# 1M_board.net
KiCad netlist of a schematic drawn in EAGLE
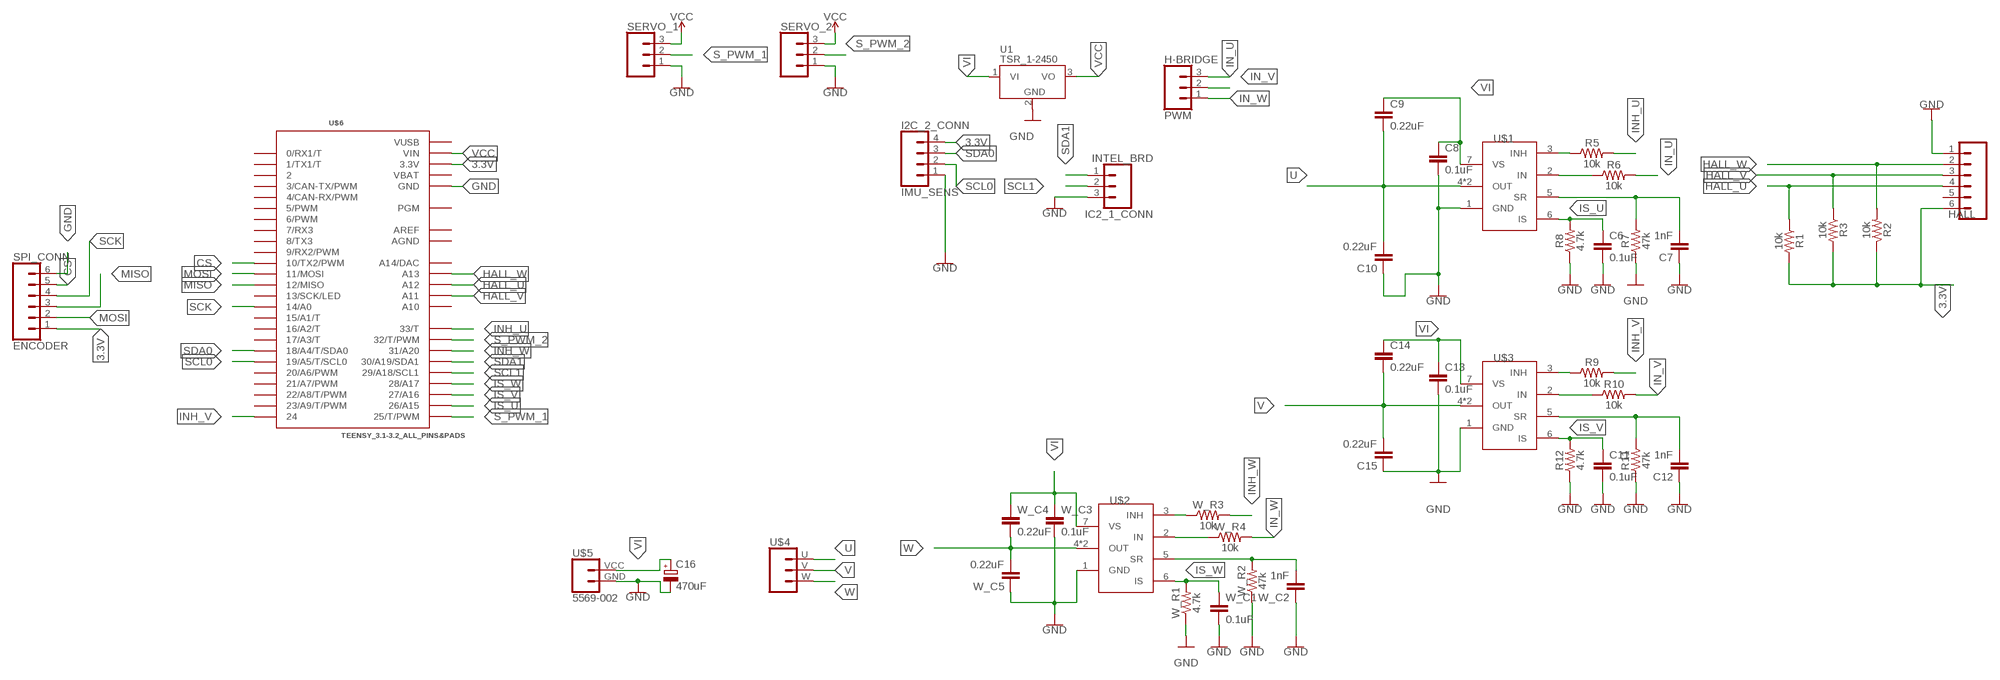
[diagram p0: schematic, sheet 1]

(export (version "E")
  (design (tool "Eeschema 10.0.6"))
  (components
    (comp (ref "C6")
      (value "0.1uF")
      (footprint "eagle-import:0603")
      (libsource (lib "eagle-import") (part "0.1UF-0603-25V-5%"))
    )
    (comp (ref "C7")
      (value "1nF")
      (footprint "eagle-import:0603")
      (libsource (lib "eagle-import") (part "1.0NF/1000PF-0603-50V-10%"))
    )
    (comp (ref "C8")
      (value "0.1uF")
      (footprint "eagle-import:0603")
      (libsource (lib "eagle-import") (part "0.1UF-0603-25V-5%"))
    )
    (comp (ref "C9")
      (value "0.22uF")
      (footprint "eagle-import:0603")
      (libsource (lib "eagle-import") (part "0.22UF-0603-25V-10%"))
    )
    (comp (ref "C10")
      (value "0.22uF")
      (footprint "eagle-import:0603")
      (libsource (lib "eagle-import") (part "0.22UF-0603-25V-10%"))
    )
    (comp (ref "C11")
      (value "0.1uF")
      (footprint "eagle-import:0603")
      (libsource (lib "eagle-import") (part "0.1UF-0603-25V-5%"))
    )
    (comp (ref "C12")
      (value "1nF")
      (footprint "eagle-import:0603")
      (libsource (lib "eagle-import") (part "1.0NF/1000PF-0603-50V-10%"))
    )
    (comp (ref "C13")
      (value "0.1uF")
      (footprint "eagle-import:0603")
      (libsource (lib "eagle-import") (part "0.1UF-0603-25V-5%"))
    )
    (comp (ref "C14")
      (value "0.22uF")
      (footprint "eagle-import:0603")
      (libsource (lib "eagle-import") (part "0.22UF-0603-25V-10%"))
    )
    (comp (ref "C15")
      (value "0.22uF")
      (footprint "eagle-import:0603")
      (libsource (lib "eagle-import") (part "0.22UF-0603-25V-10%"))
    )
    (comp (ref "C16")
      (value "470uF")
      (footprint "eagle-import:E2,5-6E")
      (libsource (lib "eagle-import") (part "CPOL-EUE2,5-6E"))
    )
    (comp (ref "H-BRIDGE")
      (value "PWM")
      (footprint "eagle-import:1X03_NO_SILK")
      (libsource (lib "eagle-import") (part "CONN_031X03_NO_SILK"))
    )
    (comp (ref "HALL")
      (value "CONN_06SMD-1MM")
      (footprint "eagle-import:1X06-1MM")
      (libsource (lib "eagle-import") (part "CONN_06SMD-1MM"))
    )
    (comp (ref "I2C_2_CONN")
      (value "IMU_SENS")
      (footprint "eagle-import:1X04_NO_SILK")
      (libsource (lib "eagle-import") (part "CONN_041X04_NO_SILK"))
    )
    (comp (ref "IC2_1_CONN")
      (value "INTEL_BRD")
      (footprint "eagle-import:1X03_NO_SILK")
      (libsource (lib "eagle-import") (part "CONN_031X03_NO_SILK"))
    )
    (comp (ref "R1")
      (value "10k")
      (footprint "eagle-import:0603")
      (libsource (lib "eagle-import") (part "10KOHM-0603-1/10W-1%"))
    )
    (comp (ref "R2")
      (value "10k")
      (footprint "eagle-import:0603")
      (libsource (lib "eagle-import") (part "10KOHM-0603-1/10W-1%"))
    )
    (comp (ref "R3")
      (value "10k")
      (footprint "eagle-import:0603")
      (libsource (lib "eagle-import") (part "10KOHM-0603-1/10W-1%"))
    )
    (comp (ref "R5")
      (value "10k")
      (footprint "eagle-import:0603")
      (libsource (lib "eagle-import") (part "10KOHM-0603-1/10W-1%"))
    )
    (comp (ref "R6")
      (value "10k")
      (footprint "eagle-import:0603")
      (libsource (lib "eagle-import") (part "10KOHM-0603-1/10W-1%"))
    )
    (comp (ref "R7")
      (value "47k")
      (footprint "eagle-import:0603")
      (libsource (lib "eagle-import") (part "47KOHM-0603-1/10W-1%"))
    )
    (comp (ref "R8")
      (value "4.7k")
      (footprint "eagle-import:0603")
      (libsource (lib "eagle-import") (part "4.7KOHM-0603-1/10W-1%"))
    )
    (comp (ref "R9")
      (value "10k")
      (footprint "eagle-import:0603")
      (libsource (lib "eagle-import") (part "10KOHM-0603-1/10W-1%"))
    )
    (comp (ref "R10")
      (value "10k")
      (footprint "eagle-import:0603")
      (libsource (lib "eagle-import") (part "10KOHM-0603-1/10W-1%"))
    )
    (comp (ref "R11")
      (value "47k")
      (footprint "eagle-import:0603")
      (libsource (lib "eagle-import") (part "47KOHM-0603-1/10W-1%"))
    )
    (comp (ref "R12")
      (value "4.7k")
      (footprint "eagle-import:0603")
      (libsource (lib "eagle-import") (part "4.7KOHM-0603-1/10W-1%"))
    )
    (comp (ref "SERVO_1")
      (value "CONN_031X03_NO_SILK")
      (footprint "eagle-import:1X03_NO_SILK")
      (libsource (lib "eagle-import") (part "CONN_031X03_NO_SILK"))
    )
    (comp (ref "SERVO_2")
      (value "CONN_031X03_NO_SILK")
      (footprint "eagle-import:1X03_NO_SILK")
      (libsource (lib "eagle-import") (part "CONN_031X03_NO_SILK"))
    )
    (comp (ref "SPI_CONN")
      (value "ENCODER")
      (footprint "eagle-import:1X06-1MM")
      (libsource (lib "eagle-import") (part "CONN_06SMD-1MM"))
    )
    (comp (ref "U$1")
      (value "IFX007TZZZZ")
      (footprint "eagle-import:P-TO263-7-1")
      (libsource (lib "eagle-import") (part "IFX007TZZZZ"))
    )
    (comp (ref "U$2")
      (value "IFX007TZZZZ")
      (footprint "eagle-import:P-TO263-7-1")
      (libsource (lib "eagle-import") (part "IFX007TZZZZ"))
    )
    (comp (ref "U$3")
      (value "IFX007TZZZZ")
      (footprint "eagle-import:P-TO263-7-1")
      (libsource (lib "eagle-import") (part "IFX007TZZZZ"))
    )
    (comp (ref "U$4")
      (value "5569-003")
      (footprint "eagle-import:5569-003")
      (libsource (lib "eagle-import") (part "5569-003"))
    )
    (comp (ref "U$5")
      (value "5569-002")
      (footprint "eagle-import:5569-002")
      (libsource (lib "eagle-import") (part "5569-002"))
    )
    (comp (ref "U$6")
      (value "TEENSY_3.1-3.2_ALL_PINS&PADS")
      (footprint "eagle-import:TEENSY_3.0-3.2_ALL_PINS_&_PADS")
      (libsource (lib "eagle-import") (part "TEENSY_3.1-3.2_ALL_PINS&PADS"))
    )
    (comp (ref "U1")
      (value "TSR_1-2450")
      (footprint "eagle-import:TSR-1")
      (libsource (lib "eagle-import") (part "TSR_1-2450"))
    )
    (comp (ref "W_C1")
      (value "0.1uF")
      (footprint "eagle-import:0603")
      (libsource (lib "eagle-import") (part "0.1UF-0603-25V-5%"))
    )
    (comp (ref "W_C2")
      (value "1nF")
      (footprint "eagle-import:0603")
      (libsource (lib "eagle-import") (part "1.0NF/1000PF-0603-50V-10%"))
    )
    (comp (ref "W_C3")
      (value "0.1uF")
      (footprint "eagle-import:0603")
      (libsource (lib "eagle-import") (part "0.1UF-0603-25V-5%"))
    )
    (comp (ref "W_C4")
      (value "0.22uF")
      (footprint "eagle-import:0603")
      (libsource (lib "eagle-import") (part "0.22UF-0603-25V-10%"))
    )
    (comp (ref "W_C5")
      (value "0.22uF")
      (footprint "eagle-import:0603")
      (libsource (lib "eagle-import") (part "0.22UF-0603-25V-10%"))
    )
    (comp (ref "W_R1")
      (value "4.7k")
      (footprint "eagle-import:0603")
      (libsource (lib "eagle-import") (part "4.7KOHM-0603-1/10W-1%"))
    )
    (comp (ref "W_R2")
      (value "47k")
      (footprint "eagle-import:0603")
      (libsource (lib "eagle-import") (part "47KOHM-0603-1/10W-1%"))
    )
    (comp (ref "W_R3")
      (value "10k")
      (footprint "eagle-import:0603")
      (libsource (lib "eagle-import") (part "10KOHM-0603-1/10W-1%"))
    )
    (comp (ref "W_R4")
      (value "10k")
      (footprint "eagle-import:0603")
      (libsource (lib "eagle-import") (part "10KOHM-0603-1/10W-1%"))
    )
  )
  (nets
    (net (code "1") (name "/AGND") (class "Default")
      (node (ref "U$6") (pin "AGND") (pinfunction "AGND_AGND") (pintype "power_in"))
    )
    (net (code "2") (name "/AREF") (class "Default")
      (node (ref "U$6") (pin "AREF") (pinfunction "AREF_AREF") (pintype "power_in"))
    )
    (net (code "3") (name "/VBAT") (class "Default")
      (node (ref "U$6") (pin "VBAT") (pinfunction "VBAT_VBAT") (pintype "power_in"))
    )
    (net (code "4") (name "/VUSB") (class "Default")
      (node (ref "U$6") (pin "VUSB") (pinfunction "VUSB_VUSB") (pintype "power_in"))
    )
    (net (code "5") (name "3.3V") (class "Default")
      (node (ref "HALL") (pin "6") (pinfunction "6_6") (pintype "passive"))
      (node (ref "I2C_2_CONN") (pin "4") (pinfunction "4_4") (pintype "passive"))
      (node (ref "R1") (pin "2") (pinfunction "2_2") (pintype "passive"))
      (node (ref "R2") (pin "1") (pinfunction "1_1") (pintype "passive"))
      (node (ref "R3") (pin "2") (pinfunction "2_2") (pintype "passive"))
      (node (ref "SPI_CONN") (pin "1") (pinfunction "1_1") (pintype "passive"))
      (node (ref "U$6") (pin "3.3V") (pinfunction "3.3V_3.3V") (pintype "power_in"))
      (node (ref "U$6") (pin "3.3V1") (pinfunction "3.3V_3.3V1") (pintype "power_in"))
      (node (ref "U$6") (pin "3.3V2") (pinfunction "3.3V_3.3V2") (pintype "power_in"))
    )
    (net (code "6") (name "CS") (class "Default")
      (node (ref "SPI_CONN") (pin "5") (pinfunction "5_5") (pintype "passive"))
      (node (ref "U$6") (pin "10") (pinfunction "10/TX2/PWM_10") (pintype "bidirectional"))
    )
    (net (code "7") (name "GND") (class "Default")
      (node (ref "C10") (pin "1") (pinfunction "1_1") (pintype "passive"))
      (node (ref "C11") (pin "2") (pinfunction "2_2") (pintype "passive"))
      (node (ref "C12") (pin "1") (pinfunction "1_1") (pintype "passive"))
      (node (ref "C13") (pin "2") (pinfunction "2_2") (pintype "passive"))
      (node (ref "C15") (pin "1") (pinfunction "1_1") (pintype "passive"))
      (node (ref "C16") (pin "-") (pinfunction "-_-") (pintype "passive"))
      (node (ref "C6") (pin "2") (pinfunction "2_2") (pintype "passive"))
      (node (ref "C7") (pin "1") (pinfunction "1_1") (pintype "passive"))
      (node (ref "C8") (pin "2") (pinfunction "2_2") (pintype "passive"))
      (node (ref "HALL") (pin "1") (pinfunction "1_1") (pintype "passive"))
      (node (ref "I2C_2_CONN") (pin "1") (pinfunction "1_1") (pintype "passive"))
      (node (ref "IC2_1_CONN") (pin "3") (pinfunction "3_3") (pintype "passive"))
      (node (ref "R11") (pin "1") (pinfunction "1_1") (pintype "passive"))
      (node (ref "R12") (pin "1") (pinfunction "1_1") (pintype "passive"))
      (node (ref "R7") (pin "1") (pinfunction "1_1") (pintype "passive"))
      (node (ref "R8") (pin "1") (pinfunction "1_1") (pintype "passive"))
      (node (ref "SERVO_1") (pin "1") (pinfunction "1_1") (pintype "passive"))
      (node (ref "SERVO_2") (pin "1") (pinfunction "1_1") (pintype "passive"))
      (node (ref "SPI_CONN") (pin "6") (pinfunction "6_6") (pintype "passive"))
      (node (ref "U$1") (pin "1") (pinfunction "GND_1") (pintype "power_in"))
      (node (ref "U$2") (pin "1") (pinfunction "GND_1") (pintype "power_in"))
      (node (ref "U$3") (pin "1") (pinfunction "GND_1") (pintype "power_in"))
      (node (ref "U$5") (pin "GND") (pinfunction "1_GND") (pintype "passive"))
      (node (ref "U$6") (pin "GND") (pinfunction "GND_GND") (pintype "power_in"))
      (node (ref "U$6") (pin "GND1") (pinfunction "GND_GND1") (pintype "power_in"))
      (node (ref "U$6") (pin "GND2") (pinfunction "GND_GND2") (pintype "power_in"))
      (node (ref "U1") (pin "2") (pinfunction "GND_2") (pintype "power_in"))
      (node (ref "W_C1") (pin "2") (pinfunction "2_2") (pintype "passive"))
      (node (ref "W_C2") (pin "1") (pinfunction "1_1") (pintype "passive"))
      (node (ref "W_C3") (pin "2") (pinfunction "2_2") (pintype "passive"))
      (node (ref "W_C5") (pin "1") (pinfunction "1_1") (pintype "passive"))
      (node (ref "W_R1") (pin "1") (pinfunction "1_1") (pintype "passive"))
      (node (ref "W_R2") (pin "1") (pinfunction "1_1") (pintype "passive"))
    )
    (net (code "8") (name "HALL_U") (class "Default")
      (node (ref "HALL") (pin "4") (pinfunction "4_4") (pintype "passive"))
      (node (ref "R1") (pin "1") (pinfunction "1_1") (pintype "passive"))
      (node (ref "U$6") (pin "A12") (pinfunction "A12_A12") (pintype "bidirectional"))
    )
    (net (code "9") (name "HALL_V") (class "Default")
      (node (ref "HALL") (pin "3") (pinfunction "3_3") (pintype "passive"))
      (node (ref "R3") (pin "1") (pinfunction "1_1") (pintype "passive"))
      (node (ref "U$6") (pin "A11") (pinfunction "A11_A11") (pintype "bidirectional"))
    )
    (net (code "10") (name "HALL_W") (class "Default")
      (node (ref "HALL") (pin "2") (pinfunction "2_2") (pintype "passive"))
      (node (ref "R2") (pin "2") (pinfunction "2_2") (pintype "passive"))
      (node (ref "U$6") (pin "A13") (pinfunction "A13_A13") (pintype "bidirectional"))
    )
    (net (code "11") (name "INH_U") (class "Default")
      (node (ref "R5") (pin "2") (pinfunction "2_2") (pintype "passive"))
      (node (ref "U$6") (pin "33") (pinfunction "33/T_33") (pintype "bidirectional"))
    )
    (net (code "12") (name "INH_V") (class "Default")
      (node (ref "R9") (pin "2") (pinfunction "2_2") (pintype "passive"))
      (node (ref "U$6") (pin "24") (pinfunction "24_24") (pintype "bidirectional"))
    )
    (net (code "13") (name "INH_W") (class "Default")
      (node (ref "U$6") (pin "31") (pinfunction "31/A20_31") (pintype "bidirectional"))
      (node (ref "W_R3") (pin "2") (pinfunction "2_2") (pintype "passive"))
    )
    (net (code "14") (name "IN_U") (class "Default")
      (node (ref "H-BRIDGE") (pin "3") (pinfunction "3_3") (pintype "passive"))
      (node (ref "R6") (pin "2") (pinfunction "2_2") (pintype "passive"))
    )
    (net (code "15") (name "IN_V") (class "Default")
      (node (ref "H-BRIDGE") (pin "2") (pinfunction "2_2") (pintype "passive"))
      (node (ref "R10") (pin "2") (pinfunction "2_2") (pintype "passive"))
    )
    (net (code "16") (name "IN_W") (class "Default")
      (node (ref "H-BRIDGE") (pin "1") (pinfunction "1_1") (pintype "passive"))
      (node (ref "W_R4") (pin "2") (pinfunction "2_2") (pintype "passive"))
    )
    (net (code "17") (name "IS_U") (class "Default")
      (node (ref "C6") (pin "1") (pinfunction "1_1") (pintype "passive"))
      (node (ref "R8") (pin "2") (pinfunction "2_2") (pintype "passive"))
      (node (ref "U$1") (pin "6") (pinfunction "IS_6") (pintype "output"))
      (node (ref "U$6") (pin "26") (pinfunction "26/A15_26") (pintype "bidirectional"))
    )
    (net (code "18") (name "IS_V") (class "Default")
      (node (ref "C11") (pin "1") (pinfunction "1_1") (pintype "passive"))
      (node (ref "R12") (pin "2") (pinfunction "2_2") (pintype "passive"))
      (node (ref "U$3") (pin "6") (pinfunction "IS_6") (pintype "output"))
      (node (ref "U$6") (pin "27") (pinfunction "27/A16_27") (pintype "bidirectional"))
    )
    (net (code "19") (name "IS_W") (class "Default")
      (node (ref "U$2") (pin "6") (pinfunction "IS_6") (pintype "output"))
      (node (ref "U$6") (pin "28") (pinfunction "28/A17_28") (pintype "bidirectional"))
      (node (ref "W_C1") (pin "1") (pinfunction "1_1") (pintype "passive"))
      (node (ref "W_R1") (pin "2") (pinfunction "2_2") (pintype "passive"))
    )
    (net (code "20") (name "MISO") (class "Default")
      (node (ref "SPI_CONN") (pin "3") (pinfunction "3_3") (pintype "passive"))
      (node (ref "U$6") (pin "12") (pinfunction "12/MISO_12") (pintype "bidirectional"))
    )
    (net (code "21") (name "MOSI") (class "Default")
      (node (ref "SPI_CONN") (pin "2") (pinfunction "2_2") (pintype "passive"))
      (node (ref "U$6") (pin "11") (pinfunction "11/MOSI_11") (pintype "bidirectional"))
    )
    (net (code "22") (name "Net-(U$1-IN)") (class "Default")
      (node (ref "R6") (pin "1") (pinfunction "1_1") (pintype "passive"))
      (node (ref "U$1") (pin "2") (pinfunction "IN_2") (pintype "input"))
    )
    (net (code "23") (name "Net-(U$1-INH)") (class "Default")
      (node (ref "R5") (pin "1") (pinfunction "1_1") (pintype "passive"))
      (node (ref "U$1") (pin "3") (pinfunction "INH_3") (pintype "bidirectional"))
    )
    (net (code "24") (name "Net-(U$1-SR)") (class "Default")
      (node (ref "C7") (pin "2") (pinfunction "2_2") (pintype "passive"))
      (node (ref "R7") (pin "2") (pinfunction "2_2") (pintype "passive"))
      (node (ref "U$1") (pin "5") (pinfunction "SR_5") (pintype "input"))
    )
    (net (code "25") (name "Net-(U$2-IN)") (class "Default")
      (node (ref "U$2") (pin "2") (pinfunction "IN_2") (pintype "input"))
      (node (ref "W_R4") (pin "1") (pinfunction "1_1") (pintype "passive"))
    )
    (net (code "26") (name "Net-(U$2-INH)") (class "Default")
      (node (ref "U$2") (pin "3") (pinfunction "INH_3") (pintype "bidirectional"))
      (node (ref "W_R3") (pin "1") (pinfunction "1_1") (pintype "passive"))
    )
    (net (code "27") (name "Net-(U$2-SR)") (class "Default")
      (node (ref "U$2") (pin "5") (pinfunction "SR_5") (pintype "input"))
      (node (ref "W_C2") (pin "2") (pinfunction "2_2") (pintype "passive"))
      (node (ref "W_R2") (pin "2") (pinfunction "2_2") (pintype "passive"))
    )
    (net (code "28") (name "Net-(U$3-IN)") (class "Default")
      (node (ref "R10") (pin "1") (pinfunction "1_1") (pintype "passive"))
      (node (ref "U$3") (pin "2") (pinfunction "IN_2") (pintype "input"))
    )
    (net (code "29") (name "Net-(U$3-INH)") (class "Default")
      (node (ref "R9") (pin "1") (pinfunction "1_1") (pintype "passive"))
      (node (ref "U$3") (pin "3") (pinfunction "INH_3") (pintype "bidirectional"))
    )
    (net (code "30") (name "Net-(U$3-SR)") (class "Default")
      (node (ref "C12") (pin "2") (pinfunction "2_2") (pintype "passive"))
      (node (ref "R11") (pin "2") (pinfunction "2_2") (pintype "passive"))
      (node (ref "U$3") (pin "5") (pinfunction "SR_5") (pintype "input"))
    )
    (net (code "31") (name "SCK") (class "Default")
      (node (ref "SPI_CONN") (pin "4") (pinfunction "4_4") (pintype "passive"))
      (node (ref "U$6") (pin "14/A0") (pinfunction "14/A0_14/A0") (pintype "bidirectional"))
    )
    (net (code "32") (name "SCL0") (class "Default")
      (node (ref "I2C_2_CONN") (pin "2") (pinfunction "2_2") (pintype "passive"))
      (node (ref "U$6") (pin "19/A5") (pinfunction "19/A5/T/SCL0_19/A5") (pintype "bidirectional"))
    )
    (net (code "33") (name "SCL1") (class "Default")
      (node (ref "IC2_1_CONN") (pin "2") (pinfunction "2_2") (pintype "passive"))
      (node (ref "U$6") (pin "29") (pinfunction "29/A18/SCL1_29") (pintype "bidirectional"))
    )
    (net (code "34") (name "SDA0") (class "Default")
      (node (ref "I2C_2_CONN") (pin "3") (pinfunction "3_3") (pintype "passive"))
      (node (ref "U$6") (pin "18/A4") (pinfunction "18/A4/T/SDA0_18/A4") (pintype "bidirectional"))
    )
    (net (code "35") (name "SDA1") (class "Default")
      (node (ref "IC2_1_CONN") (pin "1") (pinfunction "1_1") (pintype "passive"))
      (node (ref "U$6") (pin "30") (pinfunction "30/A19/SDA1_30") (pintype "bidirectional"))
    )
    (net (code "36") (name "S_PWM_1") (class "Default")
      (node (ref "SERVO_1") (pin "2") (pinfunction "2_2") (pintype "passive"))
      (node (ref "U$6") (pin "25") (pinfunction "25/T/PWM_25") (pintype "bidirectional"))
    )
    (net (code "37") (name "S_PWM_2") (class "Default")
      (node (ref "SERVO_2") (pin "2") (pinfunction "2_2") (pintype "passive"))
      (node (ref "U$6") (pin "32") (pinfunction "32/T/PWM_32") (pintype "bidirectional"))
    )
    (net (code "38") (name "U") (class "Default")
      (node (ref "C10") (pin "2") (pinfunction "2_2") (pintype "passive"))
      (node (ref "C9") (pin "2") (pinfunction "2_2") (pintype "passive"))
      (node (ref "U$1") (pin "4") (pinfunction "OUT_4") (pintype "power_in"))
      (node (ref "U$1") (pin "8") (pinfunction "OUT_8") (pintype "power_in"))
      (node (ref "U$4") (pin "U") (pinfunction "W_U") (pintype "passive"))
    )
    (net (code "39") (name "V") (class "Default")
      (node (ref "C14") (pin "2") (pinfunction "2_2") (pintype "passive"))
      (node (ref "C15") (pin "2") (pinfunction "2_2") (pintype "passive"))
      (node (ref "U$3") (pin "4") (pinfunction "OUT_4") (pintype "power_in"))
      (node (ref "U$3") (pin "8") (pinfunction "OUT_8") (pintype "power_in"))
      (node (ref "U$4") (pin "V") (pinfunction "U_V") (pintype "passive"))
    )
    (net (code "40") (name "VCC") (class "Default")
      (node (ref "SERVO_1") (pin "3") (pinfunction "3_3") (pintype "passive"))
      (node (ref "SERVO_2") (pin "3") (pinfunction "3_3") (pintype "passive"))
      (node (ref "U$6") (pin "VIN") (pinfunction "VIN_VIN") (pintype "power_in"))
      (node (ref "U1") (pin "3") (pinfunction "VO_3") (pintype "power_in"))
    )
    (net (code "41") (name "VI") (class "Default")
      (node (ref "C13") (pin "1") (pinfunction "1_1") (pintype "passive"))
      (node (ref "C14") (pin "1") (pinfunction "1_1") (pintype "passive"))
      (node (ref "C16") (pin "+") (pinfunction "+_+") (pintype "passive"))
      (node (ref "C8") (pin "1") (pinfunction "1_1") (pintype "passive"))
      (node (ref "C9") (pin "1") (pinfunction "1_1") (pintype "passive"))
      (node (ref "U$1") (pin "7") (pinfunction "VS_7") (pintype "power_in"))
      (node (ref "U$2") (pin "7") (pinfunction "VS_7") (pintype "power_in"))
      (node (ref "U$3") (pin "7") (pinfunction "VS_7") (pintype "power_in"))
      (node (ref "U$5") (pin "VCC") (pinfunction "2_VCC") (pintype "passive"))
      (node (ref "U1") (pin "1") (pinfunction "VI_1") (pintype "power_in"))
      (node (ref "W_C3") (pin "1") (pinfunction "1_1") (pintype "passive"))
      (node (ref "W_C4") (pin "1") (pinfunction "1_1") (pintype "passive"))
    )
    (net (code "42") (name "W") (class "Default")
      (node (ref "U$2") (pin "4") (pinfunction "OUT_4") (pintype "power_in"))
      (node (ref "U$2") (pin "8") (pinfunction "OUT_8") (pintype "power_in"))
      (node (ref "U$4") (pin "W") (pinfunction "V_W") (pintype "passive"))
      (node (ref "W_C4") (pin "2") (pinfunction "2_2") (pintype "passive"))
      (node (ref "W_C5") (pin "2") (pinfunction "2_2") (pintype "passive"))
    )
    (net (code "43") (name "unconnected-(HALL-Pad5)") (class "Default")
      (node (ref "HALL") (pin "5") (pinfunction "5_5") (pintype "passive"))
    )
    (net (code "44") (name "unconnected-(U$6-0{slash}RX1{slash}T-Pad0)") (class "Default")
      (node (ref "U$6") (pin "0") (pinfunction "0/RX1/T_0") (pintype "bidirectional"))
    )
    (net (code "45") (name "unconnected-(U$6-1{slash}TX1{slash}T-Pad1)") (class "Default")
      (node (ref "U$6") (pin "1") (pinfunction "1/TX1/T_1") (pintype "bidirectional"))
    )
    (net (code "46") (name "unconnected-(U$6-3{slash}CAN-TX{slash}PWM-Pad3)") (class "Default")
      (node (ref "U$6") (pin "3") (pinfunction "3/CAN-TX/PWM_3") (pintype "bidirectional"))
    )
    (net (code "47") (name "unconnected-(U$6-4{slash}CAN-RX{slash}PWM-Pad4)") (class "Default")
      (node (ref "U$6") (pin "4") (pinfunction "4/CAN-RX/PWM_4") (pintype "bidirectional"))
    )
    (net (code "48") (name "unconnected-(U$6-5{slash}PWM-Pad5)") (class "Default")
      (node (ref "U$6") (pin "5") (pinfunction "5/PWM_5") (pintype "bidirectional"))
    )
    (net (code "49") (name "unconnected-(U$6-6{slash}PWM-Pad6)") (class "Default")
      (node (ref "U$6") (pin "6") (pinfunction "6/PWM_6") (pintype "bidirectional"))
    )
    (net (code "50") (name "unconnected-(U$6-7{slash}RX3-Pad7)") (class "Default")
      (node (ref "U$6") (pin "7") (pinfunction "7/RX3_7") (pintype "bidirectional"))
    )
    (net (code "51") (name "unconnected-(U$6-8{slash}TX3-Pad8)") (class "Default")
      (node (ref "U$6") (pin "8") (pinfunction "8/TX3_8") (pintype "bidirectional"))
    )
    (net (code "52") (name "unconnected-(U$6-9{slash}RX2{slash}PWM-Pad9)") (class "Default")
      (node (ref "U$6") (pin "9") (pinfunction "9/RX2/PWM_9") (pintype "bidirectional"))
    )
    (net (code "53") (name "unconnected-(U$6-13{slash}SCK{slash}LED-Pad13)") (class "Default")
      (node (ref "U$6") (pin "13") (pinfunction "13/SCK/LED_13") (pintype "bidirectional"))
    )
    (net (code "54") (name "unconnected-(U$6-15{slash}A1{slash}T-Pad15{slash}A1)") (class "Default")
      (node (ref "U$6") (pin "15/A1") (pinfunction "15/A1/T_15/A1") (pintype "bidirectional"))
    )
    (net (code "55") (name "unconnected-(U$6-16{slash}A2{slash}T-Pad16{slash}A2)") (class "Default")
      (node (ref "U$6") (pin "16/A2") (pinfunction "16/A2/T_16/A2") (pintype "bidirectional"))
    )
    (net (code "56") (name "unconnected-(U$6-17{slash}A3{slash}T-Pad17{slash}A3)") (class "Default")
      (node (ref "U$6") (pin "17/A3") (pinfunction "17/A3/T_17/A3") (pintype "bidirectional"))
    )
    (net (code "57") (name "unconnected-(U$6-20{slash}A6{slash}PWM-Pad20{slash}A6)") (class "Default")
      (node (ref "U$6") (pin "20/A6") (pinfunction "20/A6/PWM_20/A6") (pintype "bidirectional"))
    )
    (net (code "58") (name "unconnected-(U$6-21{slash}A7{slash}PWM-Pad21{slash}A7)") (class "Default")
      (node (ref "U$6") (pin "21/A7") (pinfunction "21/A7/PWM_21/A7") (pintype "bidirectional"))
    )
    (net (code "59") (name "unconnected-(U$6-22{slash}A8{slash}T{slash}PWM-Pad22{slash}A8)") (class "Default")
      (node (ref "U$6") (pin "22/A8") (pinfunction "22/A8/T/PWM_22/A8") (pintype "bidirectional"))
    )
    (net (code "60") (name "unconnected-(U$6-23{slash}A9{slash}T{slash}PWM-Pad23{slash}A9)") (class "Default")
      (node (ref "U$6") (pin "23/A9") (pinfunction "23/A9/T/PWM_23/A9") (pintype "bidirectional"))
    )
    (net (code "61") (name "unconnected-(U$6-A14{slash}DAC-PadRESET{slash}DAC)") (class "Default")
      (node (ref "U$6") (pin "RESET/DAC") (pinfunction "A14/DAC_RESET/DAC") (pintype "bidirectional"))
    )
    (net (code "62") (name "unconnected-(U$6-Pad2)") (class "Default")
      (node (ref "U$6") (pin "2") (pinfunction "2_2") (pintype "bidirectional"))
    )
    (net (code "63") (name "unconnected-(U$6-PadA10)") (class "Default")
      (node (ref "U$6") (pin "A10") (pinfunction "A10_A10") (pintype "bidirectional"))
    )
    (net (code "64") (name "unconnected-(U$6-PadPGM)") (class "Default")
      (node (ref "U$6") (pin "PGM") (pinfunction "PGM_PGM") (pintype "bidirectional"))
    )
  )
)
